# adc.net
KiCad netlist of a schematic drawn in EAGLE
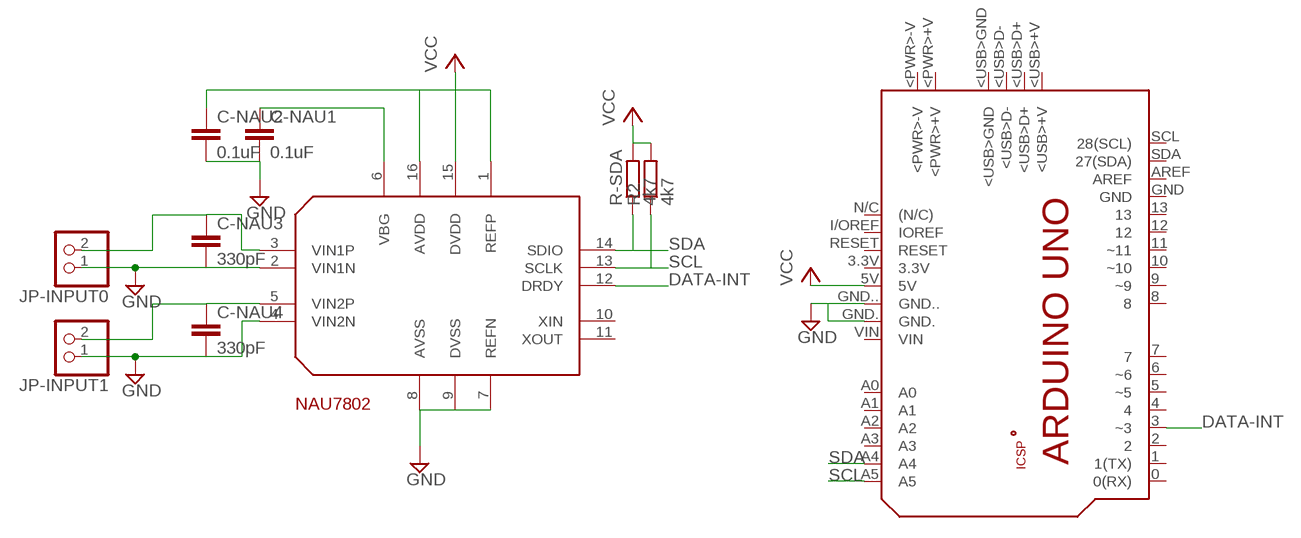
[diagram p0: schematic, sheet 1]

(export (version "E")
  (design (tool "Eeschema 10.0.6"))
  (components
    (comp (ref "C-NAU1")
      (value "0.1uF")
      (footprint "eagle-import:C050-024X044")
      (libsource (lib "eagle-import") (part "C-EU050-024X044"))
    )
    (comp (ref "C-NAU2")
      (value "0.1uF")
      (footprint "eagle-import:C050-024X044")
      (libsource (lib "eagle-import") (part "C-EU050-024X044"))
    )
    (comp (ref "C-NAU3")
      (value "330pF")
      (footprint "eagle-import:C050-024X044")
      (libsource (lib "eagle-import") (part "C-EU050-024X044"))
    )
    (comp (ref "C-NAU4")
      (value "330pF")
      (footprint "eagle-import:C050-024X044")
      (libsource (lib "eagle-import") (part "C-EU050-024X044"))
    )
    (comp (ref "JP-INPUT0")
      (value "PINHD-1X2")
      (footprint "eagle-import:1X02")
      (libsource (lib "eagle-import") (part "PINHD-1X2"))
    )
    (comp (ref "JP-INPUT1")
      (value "PINHD-1X2")
      (footprint "eagle-import:1X02")
      (libsource (lib "eagle-import") (part "PINHD-1X2"))
    )
    (comp (ref "PCB1")
      (value "ARDUINO_UNO")
      (footprint "eagle-import:ARDUINO_UNO")
      (libsource (lib "eagle-import") (part "ARDUINO_UNO"))
    )
    (comp (ref "R-SDA")
      (value "4k7")
      (footprint "eagle-import:0204_7")
      (libsource (lib "eagle-import") (part "R-EU_0204/7"))
    )
    (comp (ref "R2")
      (value "4k7")
      (footprint "eagle-import:0204_7")
      (libsource (lib "eagle-import") (part "R-EU_0204/7"))
    )
    (comp (ref "U$1")
      (value "NAU7802_DIP")
      (footprint "eagle-import:DIP16")
      (libsource (lib "eagle-import") (part "NAU7802_DIP"))
    )
  )
  (nets
    (net (code "1") (name "/DATA-INT") (class "Default")
      (node (ref "PCB1") (pin "3") (pinfunction "~{3}_3") (pintype "bidirectional"))
      (node (ref "U$1") (pin "12") (pinfunction "DRDY_12") (pintype "bidirectional"))
    )
    (net (code "2") (name "/SCL") (class "Default")
      (node (ref "PCB1") (pin "A5") (pinfunction "A5_A5") (pintype "bidirectional"))
      (node (ref "R2") (pin "1") (pinfunction "1_1") (pintype "passive"))
      (node (ref "U$1") (pin "13") (pinfunction "SCLK_13") (pintype "bidirectional"))
    )
    (net (code "3") (name "/SDA") (class "Default")
      (node (ref "PCB1") (pin "A4") (pinfunction "A4_A4") (pintype "bidirectional"))
      (node (ref "R-SDA") (pin "1") (pinfunction "1_1") (pintype "passive"))
      (node (ref "U$1") (pin "14") (pinfunction "SDIO_14") (pintype "bidirectional"))
    )
    (net (code "4") (name "GND") (class "Default")
      (node (ref "C-NAU1") (pin "2") (pinfunction "2_2") (pintype "passive"))
      (node (ref "C-NAU2") (pin "2") (pinfunction "2_2") (pintype "passive"))
      (node (ref "C-NAU3") (pin "2") (pinfunction "2_2") (pintype "passive"))
      (node (ref "C-NAU4") (pin "2") (pinfunction "2_2") (pintype "passive"))
      (node (ref "JP-INPUT0") (pin "1") (pinfunction "1_1") (pintype "passive"))
      (node (ref "JP-INPUT1") (pin "1") (pinfunction "1_1") (pintype "passive"))
      (node (ref "PCB1") (pin "GND.") (pinfunction "GND._GND.") (pintype "bidirectional"))
      (node (ref "PCB1") (pin "GND..") (pinfunction "GND.._GND..") (pintype "bidirectional"))
      (node (ref "U$1") (pin "2") (pinfunction "VIN1N_2") (pintype "bidirectional"))
      (node (ref "U$1") (pin "4") (pinfunction "VIN2N_4") (pintype "bidirectional"))
      (node (ref "U$1") (pin "7") (pinfunction "REFN_7") (pintype "bidirectional"))
      (node (ref "U$1") (pin "8") (pinfunction "AVSS_8") (pintype "bidirectional"))
      (node (ref "U$1") (pin "9") (pinfunction "DVSS_9") (pintype "bidirectional"))
    )
    (net (code "5") (name "Net-(U$1-VBG)") (class "Default")
      (node (ref "C-NAU1") (pin "1") (pinfunction "1_1") (pintype "passive"))
      (node (ref "U$1") (pin "6") (pinfunction "VBG_6") (pintype "bidirectional"))
    )
    (net (code "6") (name "Net-(U$1-VIN1P)") (class "Default")
      (node (ref "C-NAU3") (pin "1") (pinfunction "1_1") (pintype "passive"))
      (node (ref "JP-INPUT0") (pin "2") (pinfunction "2_2") (pintype "passive"))
      (node (ref "U$1") (pin "3") (pinfunction "VIN1P_3") (pintype "bidirectional"))
    )
    (net (code "7") (name "Net-(U$1-VIN2P)") (class "Default")
      (node (ref "C-NAU4") (pin "1") (pinfunction "1_1") (pintype "passive"))
      (node (ref "JP-INPUT1") (pin "2") (pinfunction "2_2") (pintype "passive"))
      (node (ref "U$1") (pin "5") (pinfunction "VIN2P_5") (pintype "bidirectional"))
    )
    (net (code "8") (name "VCC") (class "Default")
      (node (ref "C-NAU2") (pin "1") (pinfunction "1_1") (pintype "passive"))
      (node (ref "PCB1") (pin "5V") (pinfunction "5V_5V") (pintype "bidirectional"))
      (node (ref "R-SDA") (pin "2") (pinfunction "2_2") (pintype "passive"))
      (node (ref "R2") (pin "2") (pinfunction "2_2") (pintype "passive"))
      (node (ref "U$1") (pin "1") (pinfunction "REFP_1") (pintype "bidirectional"))
      (node (ref "U$1") (pin "15") (pinfunction "DVDD_15") (pintype "bidirectional"))
      (node (ref "U$1") (pin "16") (pinfunction "AVDD_16") (pintype "bidirectional"))
    )
    (net (code "9") (name "unconnected-(PCB1-(N{slash}C)-PadN{slash}C)") (class "Default")
      (node (ref "PCB1") (pin "N/C") (pinfunction "(N/C)_N/C") (pintype "bidirectional"))
    )
    (net (code "10") (name "unconnected-(PCB1-0(RX)-Pad0)") (class "Default")
      (node (ref "PCB1") (pin "0") (pinfunction "0(RX)_0") (pintype "bidirectional"))
    )
    (net (code "11") (name "unconnected-(PCB1-1(TX)-Pad1)") (class "Default")
      (node (ref "PCB1") (pin "1") (pinfunction "1(TX)_1") (pintype "bidirectional"))
    )
    (net (code "12") (name "unconnected-(PCB1-27(SDA)-PadSDA)") (class "Default")
      (node (ref "PCB1") (pin "SDA") (pinfunction "27(SDA)_SDA") (pintype "bidirectional"))
    )
    (net (code "13") (name "unconnected-(PCB1-28(SCL)-PadSCL)") (class "Default")
      (node (ref "PCB1") (pin "SCL") (pinfunction "28(SCL)_SCL") (pintype "bidirectional"))
    )
    (net (code "14") (name "unconnected-(PCB1-IOREF-PadI{slash}OREF)") (class "Default")
      (node (ref "PCB1") (pin "I/OREF") (pinfunction "IOREF_I/OREF") (pintype "bidirectional"))
    )
    (net (code "15") (name "unconnected-(PCB1-Pad+5V)") (class "Default")
      (node (ref "PCB1") (pin "+5V") (pinfunction "+5V_+5V") (pintype "bidirectional"))
    )
    (net (code "16") (name "unconnected-(PCB1-Pad2)") (class "Default")
      (node (ref "PCB1") (pin "2") (pinfunction "2_2") (pintype "bidirectional"))
    )
    (net (code "17") (name "unconnected-(PCB1-Pad3.3V)") (class "Default")
      (node (ref "PCB1") (pin "3.3V") (pinfunction "3.3V_3.3V") (pintype "bidirectional"))
    )
    (net (code "18") (name "unconnected-(PCB1-Pad4)") (class "Default")
      (node (ref "PCB1") (pin "4") (pinfunction "4_4") (pintype "bidirectional"))
    )
    (net (code "19") (name "unconnected-(PCB1-Pad7)") (class "Default")
      (node (ref "PCB1") (pin "7") (pinfunction "7_7") (pintype "bidirectional"))
    )
    (net (code "20") (name "unconnected-(PCB1-Pad8)") (class "Default")
      (node (ref "PCB1") (pin "8") (pinfunction "8_8") (pintype "bidirectional"))
    )
    (net (code "21") (name "unconnected-(PCB1-Pad12)") (class "Default")
      (node (ref "PCB1") (pin "12") (pinfunction "12_12") (pintype "bidirectional"))
    )
    (net (code "22") (name "unconnected-(PCB1-Pad13)") (class "Default")
      (node (ref "PCB1") (pin "13") (pinfunction "13_13") (pintype "bidirectional"))
    )
    (net (code "23") (name "unconnected-(PCB1-Pad<PWR>+V)") (class "Default")
      (node (ref "PCB1") (pin "<PWR>+V") (pinfunction "<PWR>+V_<PWR>+V") (pintype "bidirectional"))
    )
    (net (code "24") (name "unconnected-(PCB1-Pad<PWR>-V)") (class "Default")
      (node (ref "PCB1") (pin "<PWR>-V") (pinfunction "<PWR>-V_<PWR>-V") (pintype "bidirectional"))
    )
    (net (code "25") (name "unconnected-(PCB1-Pad<USB>+V)") (class "Default")
      (node (ref "PCB1") (pin "<USB>+V") (pinfunction "<USB>+V_<USB>+V") (pintype "bidirectional"))
    )
    (net (code "26") (name "unconnected-(PCB1-Pad<USB>D+)") (class "Default")
      (node (ref "PCB1") (pin "<USB>D+") (pinfunction "<USB>D+_<USB>D+") (pintype "bidirectional"))
    )
    (net (code "27") (name "unconnected-(PCB1-Pad<USB>D-)") (class "Default")
      (node (ref "PCB1") (pin "<USB>D-") (pinfunction "<USB>D-_<USB>D-") (pintype "bidirectional"))
    )
    (net (code "28") (name "unconnected-(PCB1-Pad<USB>GND)") (class "Default")
      (node (ref "PCB1") (pin "<USB>GND") (pinfunction "<USB>GND_<USB>GND") (pintype "bidirectional"))
    )
    (net (code "29") (name "unconnected-(PCB1-PadA0)") (class "Default")
      (node (ref "PCB1") (pin "A0") (pinfunction "A0_A0") (pintype "bidirectional"))
    )
    (net (code "30") (name "unconnected-(PCB1-PadA1)") (class "Default")
      (node (ref "PCB1") (pin "A1") (pinfunction "A1_A1") (pintype "bidirectional"))
    )
    (net (code "31") (name "unconnected-(PCB1-PadA2)") (class "Default")
      (node (ref "PCB1") (pin "A2") (pinfunction "A2_A2") (pintype "bidirectional"))
    )
    (net (code "32") (name "unconnected-(PCB1-PadA3)") (class "Default")
      (node (ref "PCB1") (pin "A3") (pinfunction "A3_A3") (pintype "bidirectional"))
    )
    (net (code "33") (name "unconnected-(PCB1-PadAREF)") (class "Default")
      (node (ref "PCB1") (pin "AREF") (pinfunction "AREF_AREF") (pintype "bidirectional"))
    )
    (net (code "34") (name "unconnected-(PCB1-PadGND)") (class "Default")
      (node (ref "PCB1") (pin "GND") (pinfunction "GND_GND") (pintype "bidirectional"))
    )
    (net (code "35") (name "unconnected-(PCB1-PadGND_)") (class "Default")
      (node (ref "PCB1") (pin "GND_") (pinfunction "GND__GND_") (pintype "bidirectional"))
    )
    (net (code "36") (name "unconnected-(PCB1-PadMISO)") (class "Default")
      (node (ref "PCB1") (pin "MISO") (pinfunction "MISO_MISO") (pintype "bidirectional"))
    )
    (net (code "37") (name "unconnected-(PCB1-PadMOSI)") (class "Default")
      (node (ref "PCB1") (pin "MOSI") (pinfunction "MOSI_MOSI") (pintype "bidirectional"))
    )
    (net (code "38") (name "unconnected-(PCB1-PadRESET)") (class "Default")
      (node (ref "PCB1") (pin "RESET") (pinfunction "RESET_RESET") (pintype "bidirectional"))
    )
    (net (code "39") (name "unconnected-(PCB1-PadRESET.)") (class "Default")
      (node (ref "PCB1") (pin "RESET.") (pinfunction "RESET._RESET.") (pintype "bidirectional"))
    )
    (net (code "40") (name "unconnected-(PCB1-PadSCK)") (class "Default")
      (node (ref "PCB1") (pin "SCK") (pinfunction "SCK_SCK") (pintype "bidirectional"))
    )
    (net (code "41") (name "unconnected-(PCB1-PadVIN)") (class "Default")
      (node (ref "PCB1") (pin "VIN") (pinfunction "VIN_VIN") (pintype "bidirectional"))
    )
    (net (code "42") (name "unconnected-(PCB1-~{5}-Pad5)") (class "Default")
      (node (ref "PCB1") (pin "5") (pinfunction "~{5}_5") (pintype "bidirectional"))
    )
    (net (code "43") (name "unconnected-(PCB1-~{6}-Pad6)") (class "Default")
      (node (ref "PCB1") (pin "6") (pinfunction "~{6}_6") (pintype "bidirectional"))
    )
    (net (code "44") (name "unconnected-(PCB1-~{9}-Pad9)") (class "Default")
      (node (ref "PCB1") (pin "9") (pinfunction "~{9}_9") (pintype "bidirectional"))
    )
    (net (code "45") (name "unconnected-(PCB1-~{10}-Pad10)") (class "Default")
      (node (ref "PCB1") (pin "10") (pinfunction "~{10}_10") (pintype "bidirectional"))
    )
    (net (code "46") (name "unconnected-(PCB1-~{11}-Pad11)") (class "Default")
      (node (ref "PCB1") (pin "11") (pinfunction "~{11}_11") (pintype "bidirectional"))
    )
    (net (code "47") (name "unconnected-(U$1-XIN-Pad10)") (class "Default")
      (node (ref "U$1") (pin "10") (pinfunction "XIN_10") (pintype "bidirectional"))
    )
    (net (code "48") (name "unconnected-(U$1-XOUT-Pad11)") (class "Default")
      (node (ref "U$1") (pin "11") (pinfunction "XOUT_11") (pintype "bidirectional"))
    )
  )
)
